# BlackChat_China_Rx.net
KiCad netlist of a schematic drawn in Altium Designer
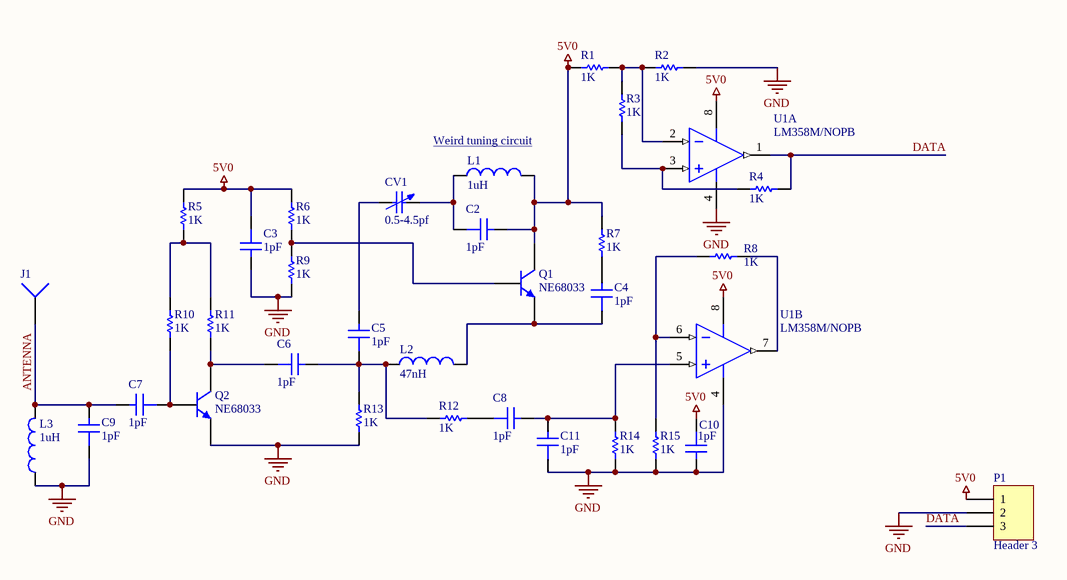
[diagram p0: BlackChat China Rx.SchDoc]

(export (version "E")
  (design (tool "Eeschema 10.0.6"))
  (components
    (comp (ref "C2")
      (value "1pF")
      (footprint "CAP-0805")
      (description "SMD Chip Capacitor")
      (libsource (lib "BlackChat Library") (part "CHIP-CAP"))
    )
    (comp (ref "C3")
      (value "1pF")
      (footprint "CAP-0805")
      (description "SMD Chip Capacitor")
      (libsource (lib "BlackChat Library") (part "CHIP-CAP"))
    )
    (comp (ref "C4")
      (value "1pF")
      (footprint "CAP-0805")
      (description "SMD Chip Capacitor")
      (libsource (lib "BlackChat Library") (part "CHIP-CAP"))
    )
    (comp (ref "C5")
      (value "1pF")
      (footprint "CAP-0805")
      (description "SMD Chip Capacitor")
      (libsource (lib "BlackChat Library") (part "CHIP-CAP"))
    )
    (comp (ref "C6")
      (value "1pF")
      (footprint "CAP-0805")
      (description "SMD Chip Capacitor")
      (libsource (lib "BlackChat Library") (part "CHIP-CAP"))
    )
    (comp (ref "C7")
      (value "1pF")
      (footprint "CAP-0805")
      (description "SMD Chip Capacitor")
      (libsource (lib "BlackChat Library") (part "CHIP-CAP"))
    )
    (comp (ref "C8")
      (value "1pF")
      (footprint "CAP-0805")
      (description "SMD Chip Capacitor")
      (libsource (lib "BlackChat Library") (part "CHIP-CAP"))
    )
    (comp (ref "C9")
      (value "1pF")
      (footprint "CAP-0805")
      (description "SMD Chip Capacitor")
      (libsource (lib "BlackChat Library") (part "CHIP-CAP"))
    )
    (comp (ref "C10")
      (value "1pF")
      (footprint "CAP-0805")
      (description "SMD Chip Capacitor")
      (libsource (lib "BlackChat Library") (part "CHIP-CAP"))
    )
    (comp (ref "C11")
      (value "1pF")
      (footprint "CAP-0805")
      (description "SMD Chip Capacitor")
      (libsource (lib "BlackChat Library") (part "CHIP-CAP"))
    )
    (comp (ref "CV1")
      (value "0.5-4.5pf")
      (footprint "CAP-GSX364")
      (description "0.5pF to 4.5pF variable capacitor.")
      (libsource (lib "BlackChat Library") (part "GSX364"))
    )
    (comp (ref "J1")
      (value "Socket")
      (footprint "PIN1")
      (fields (field (name "PUBLISHER") "Altium Limited"))
      (libsource (lib "Miscellaneous Connectors") (part "Socket"))
    )
    (comp (ref "L1")
      (value "1uH")
      (footprint "C1210")
      (description "Generic Inductor")
      (libsource (lib "BlackChat Library") (part "Inductor"))
    )
    (comp (ref "L2")
      (value "47nH")
      (footprint "C1210")
      (description "Generic Inductor")
      (libsource (lib "BlackChat Library") (part "Inductor"))
    )
    (comp (ref "L3")
      (value "1uH")
      (footprint "AXIAL-0.3")
      (description "Generic Inductor")
      (libsource (lib "BlackChat Library") (part "Inductor"))
    )
    (comp (ref "P1")
      (value "Header 3")
      (footprint "HDR1X3")
      (description "Header, 3-Pin")
      (fields (field (name "PUBLISHER") "Altium Limited"))
      (libsource (lib "Miscellaneous Connectors") (part "Header 3"))
    )
    (comp (ref "Q1")
      (value "NE68033")
      (footprint "SOT95P275X120-3N")
      (description "NPN SILICON HIGH FREQUENCY TRANSISTOR")
      (libsource (lib "BlackChat Library") (part "NE68033"))
    )
    (comp (ref "Q2")
      (value "NE68033")
      (footprint "SOT95P275X120-3N")
      (description "NPN SILICON HIGH FREQUENCY TRANSISTOR")
      (libsource (lib "BlackChat Library") (part "NE68033"))
    )
    (comp (ref "R1")
      (value "1K")
      (footprint "RES-0805")
      (description "SMD Chip Resistor")
      (libsource (lib "BlackChat Library") (part "CHIP-RES"))
    )
    (comp (ref "R2")
      (value "1K")
      (footprint "RES-0805")
      (description "SMD Chip Resistor")
      (libsource (lib "BlackChat Library") (part "CHIP-RES"))
    )
    (comp (ref "R3")
      (value "1K")
      (footprint "RES-0805")
      (description "SMD Chip Resistor")
      (libsource (lib "BlackChat Library") (part "CHIP-RES"))
    )
    (comp (ref "R4")
      (value "1K")
      (footprint "RES-0805")
      (description "SMD Chip Resistor")
      (libsource (lib "BlackChat Library") (part "CHIP-RES"))
    )
    (comp (ref "R5")
      (value "1K")
      (footprint "RES-0805")
      (description "SMD Chip Resistor")
      (libsource (lib "BlackChat Library") (part "CHIP-RES"))
    )
    (comp (ref "R6")
      (value "1K")
      (footprint "RES-0805")
      (description "SMD Chip Resistor")
      (libsource (lib "BlackChat Library") (part "CHIP-RES"))
    )
    (comp (ref "R7")
      (value "1K")
      (footprint "RES-0805")
      (description "SMD Chip Resistor")
      (libsource (lib "BlackChat Library") (part "CHIP-RES"))
    )
    (comp (ref "R8")
      (value "1K")
      (footprint "RES-0805")
      (description "SMD Chip Resistor")
      (libsource (lib "BlackChat Library") (part "CHIP-RES"))
    )
    (comp (ref "R9")
      (value "1K")
      (footprint "RES-0805")
      (description "SMD Chip Resistor")
      (libsource (lib "BlackChat Library") (part "CHIP-RES"))
    )
    (comp (ref "R10")
      (value "1K")
      (footprint "RES-0805")
      (description "SMD Chip Resistor")
      (libsource (lib "BlackChat Library") (part "CHIP-RES"))
    )
    (comp (ref "R11")
      (value "1K")
      (footprint "RES-0805")
      (description "SMD Chip Resistor")
      (libsource (lib "BlackChat Library") (part "CHIP-RES"))
    )
    (comp (ref "R12")
      (value "1K")
      (footprint "RES-0805")
      (description "SMD Chip Resistor")
      (libsource (lib "BlackChat Library") (part "CHIP-RES"))
    )
    (comp (ref "R13")
      (value "1K")
      (footprint "RES-0805")
      (description "SMD Chip Resistor")
      (libsource (lib "BlackChat Library") (part "CHIP-RES"))
    )
    (comp (ref "R14")
      (value "1K")
      (footprint "RES-0805")
      (description "SMD Chip Resistor")
      (libsource (lib "BlackChat Library") (part "CHIP-RES"))
    )
    (comp (ref "R15")
      (value "1K")
      (footprint "RES-0805")
      (description "SMD Chip Resistor")
      (libsource (lib "BlackChat Library") (part "CHIP-RES"))
    )
    (comp (ref "U1")
      (value "LM358M/NOPB")
      (footprint "M08A_L")
      (description "Low Power Dual Operational Amplifier, 8-pin Narrow SOIC, Pb-Free")
      (fields (field (name "MANUFACTURER") "National Semiconductor"))
      (libsource (lib "Altium Content Vault") (part "AMP-OPA-LM158-8"))
    )
  )
  (nets
    (net (code "1") (name "/ANTENNA") (class "Default")
      (node (ref "C7") (pin "2") (pinfunction "2_2") (pintype "passive"))
      (node (ref "C9") (pin "2") (pinfunction "2_2") (pintype "passive"))
      (node (ref "J1") (pin "1") (pinfunction "1_1") (pintype "passive"))
      (node (ref "L3") (pin "2") (pinfunction "2_2") (pintype "passive"))
    )
    (net (code "2") (name "/DATA") (class "Default")
      (node (ref "P1") (pin "3") (pinfunction "3_3") (pintype "passive"))
      (node (ref "R4") (pin "2") (pinfunction "2_2") (pintype "passive"))
      (node (ref "U1") (pin "1") (pinfunction "OUTA_1") (pintype "output"))
    )
    (net (code "3") (name "5V0") (class "Default")
      (node (ref "C10") (pin "1") (pinfunction "1_1") (pintype "passive"))
      (node (ref "C2") (pin "2") (pinfunction "2_2") (pintype "passive"))
      (node (ref "C3") (pin "1") (pinfunction "1_1") (pintype "passive"))
      (node (ref "L1") (pin "2") (pinfunction "2_2") (pintype "passive"))
      (node (ref "P1") (pin "1") (pinfunction "1_1") (pintype "passive"))
      (node (ref "Q1") (pin "3") (pinfunction "C_3") (pintype "passive"))
      (node (ref "R1") (pin "2") (pinfunction "2_2") (pintype "passive"))
      (node (ref "R5") (pin "2") (pinfunction "2_2") (pintype "passive"))
      (node (ref "R6") (pin "2") (pinfunction "2_2") (pintype "passive"))
      (node (ref "R7") (pin "1") (pinfunction "1_1") (pintype "passive"))
      (node (ref "U1") (pin "8") (pinfunction "V+_8") (pintype "power_in"))
    )
    (net (code "4") (name "GND") (class "Default")
      (node (ref "C10") (pin "2") (pinfunction "2_2") (pintype "passive"))
      (node (ref "C11") (pin "1") (pinfunction "1_1") (pintype "passive"))
      (node (ref "C3") (pin "2") (pinfunction "2_2") (pintype "passive"))
      (node (ref "C9") (pin "1") (pinfunction "1_1") (pintype "passive"))
      (node (ref "L3") (pin "1") (pinfunction "1_1") (pintype "passive"))
      (node (ref "P1") (pin "2") (pinfunction "2_2") (pintype "passive"))
      (node (ref "Q2") (pin "1") (pinfunction "E_1") (pintype "passive"))
      (node (ref "R13") (pin "1") (pinfunction "1_1") (pintype "passive"))
      (node (ref "R14") (pin "2") (pinfunction "2_2") (pintype "passive"))
      (node (ref "R15") (pin "2") (pinfunction "2_2") (pintype "passive"))
      (node (ref "R2") (pin "1") (pinfunction "1_1") (pintype "passive"))
      (node (ref "R9") (pin "1") (pinfunction "1_1") (pintype "passive"))
      (node (ref "U1") (pin "4") (pinfunction "GND_4") (pintype "power_in"))
    )
    (net (code "5") (name "Net-(C2-Pad1)") (class "Default")
      (node (ref "C2") (pin "1") (pinfunction "1_1") (pintype "passive"))
      (node (ref "CV1") (pin "2") (pinfunction "2_2") (pintype "passive"))
      (node (ref "L1") (pin "1") (pinfunction "1_1") (pintype "passive"))
    )
    (net (code "6") (name "Net-(C4-Pad2)") (class "Default")
      (node (ref "C4") (pin "2") (pinfunction "2_2") (pintype "passive"))
      (node (ref "R7") (pin "2") (pinfunction "2_2") (pintype "passive"))
    )
    (net (code "7") (name "Net-(C5-Pad1)") (class "Default")
      (node (ref "C5") (pin "1") (pinfunction "1_1") (pintype "passive"))
      (node (ref "C6") (pin "2") (pinfunction "2_2") (pintype "passive"))
      (node (ref "L2") (pin "1") (pinfunction "1_1") (pintype "passive"))
      (node (ref "R12") (pin "2") (pinfunction "2_2") (pintype "passive"))
      (node (ref "R13") (pin "2") (pinfunction "2_2") (pintype "passive"))
    )
    (net (code "8") (name "Net-(C5-Pad2)") (class "Default")
      (node (ref "C5") (pin "2") (pinfunction "2_2") (pintype "passive"))
      (node (ref "CV1") (pin "1") (pinfunction "1_1") (pintype "passive"))
    )
    (net (code "9") (name "Net-(C8-Pad1)") (class "Default")
      (node (ref "C8") (pin "1") (pinfunction "1_1") (pintype "passive"))
      (node (ref "R12") (pin "1") (pinfunction "1_1") (pintype "passive"))
    )
    (net (code "10") (name "Net-(Q1-B)") (class "Default")
      (node (ref "Q1") (pin "2") (pinfunction "B_2") (pintype "passive"))
      (node (ref "R6") (pin "1") (pinfunction "1_1") (pintype "passive"))
      (node (ref "R9") (pin "2") (pinfunction "2_2") (pintype "passive"))
    )
    (net (code "11") (name "Net-(Q1-E)") (class "Default")
      (node (ref "C4") (pin "1") (pinfunction "1_1") (pintype "passive"))
      (node (ref "L2") (pin "2") (pinfunction "2_2") (pintype "passive"))
      (node (ref "Q1") (pin "1") (pinfunction "E_1") (pintype "passive"))
    )
    (net (code "12") (name "Net-(Q2-B)") (class "Default")
      (node (ref "C7") (pin "1") (pinfunction "1_1") (pintype "passive"))
      (node (ref "Q2") (pin "2") (pinfunction "B_2") (pintype "passive"))
      (node (ref "R10") (pin "1") (pinfunction "1_1") (pintype "passive"))
    )
    (net (code "13") (name "Net-(Q2-C)") (class "Default")
      (node (ref "C6") (pin "1") (pinfunction "1_1") (pintype "passive"))
      (node (ref "Q2") (pin "3") (pinfunction "C_3") (pintype "passive"))
      (node (ref "R11") (pin "1") (pinfunction "1_1") (pintype "passive"))
    )
    (net (code "14") (name "Net-(R10-Pad2)") (class "Default")
      (node (ref "R10") (pin "2") (pinfunction "2_2") (pintype "passive"))
      (node (ref "R11") (pin "2") (pinfunction "2_2") (pintype "passive"))
      (node (ref "R5") (pin "1") (pinfunction "1_1") (pintype "passive"))
    )
    (net (code "15") (name "Net-(U1A-INA+)") (class "Default")
      (node (ref "R3") (pin "2") (pinfunction "2_2") (pintype "passive"))
      (node (ref "R4") (pin "1") (pinfunction "1_1") (pintype "passive"))
      (node (ref "U1") (pin "3") (pinfunction "INA+_3") (pintype "input"))
    )
    (net (code "16") (name "Net-(U1A-INA-)") (class "Default")
      (node (ref "R1") (pin "1") (pinfunction "1_1") (pintype "passive"))
      (node (ref "R2") (pin "2") (pinfunction "2_2") (pintype "passive"))
      (node (ref "R3") (pin "1") (pinfunction "1_1") (pintype "passive"))
      (node (ref "U1") (pin "2") (pinfunction "INA-_2") (pintype "input"))
    )
    (net (code "17") (name "Net-(U1B-INB+)") (class "Default")
      (node (ref "C11") (pin "2") (pinfunction "2_2") (pintype "passive"))
      (node (ref "C8") (pin "2") (pinfunction "2_2") (pintype "passive"))
      (node (ref "R14") (pin "1") (pinfunction "1_1") (pintype "passive"))
      (node (ref "U1") (pin "5") (pinfunction "INB+_5") (pintype "input"))
    )
    (net (code "18") (name "Net-(U1B-INB-)") (class "Default")
      (node (ref "R15") (pin "1") (pinfunction "1_1") (pintype "passive"))
      (node (ref "R8") (pin "1") (pinfunction "1_1") (pintype "passive"))
      (node (ref "U1") (pin "6") (pinfunction "INB-_6") (pintype "input"))
    )
    (net (code "19") (name "Net-(U1B-OUTB)") (class "Default")
      (node (ref "R8") (pin "2") (pinfunction "2_2") (pintype "passive"))
      (node (ref "U1") (pin "7") (pinfunction "OUTB_7") (pintype "output"))
    )
  )
)
